# ANISMADriverBoard_v03.net
KiCad netlist of a schematic drawn in EAGLE
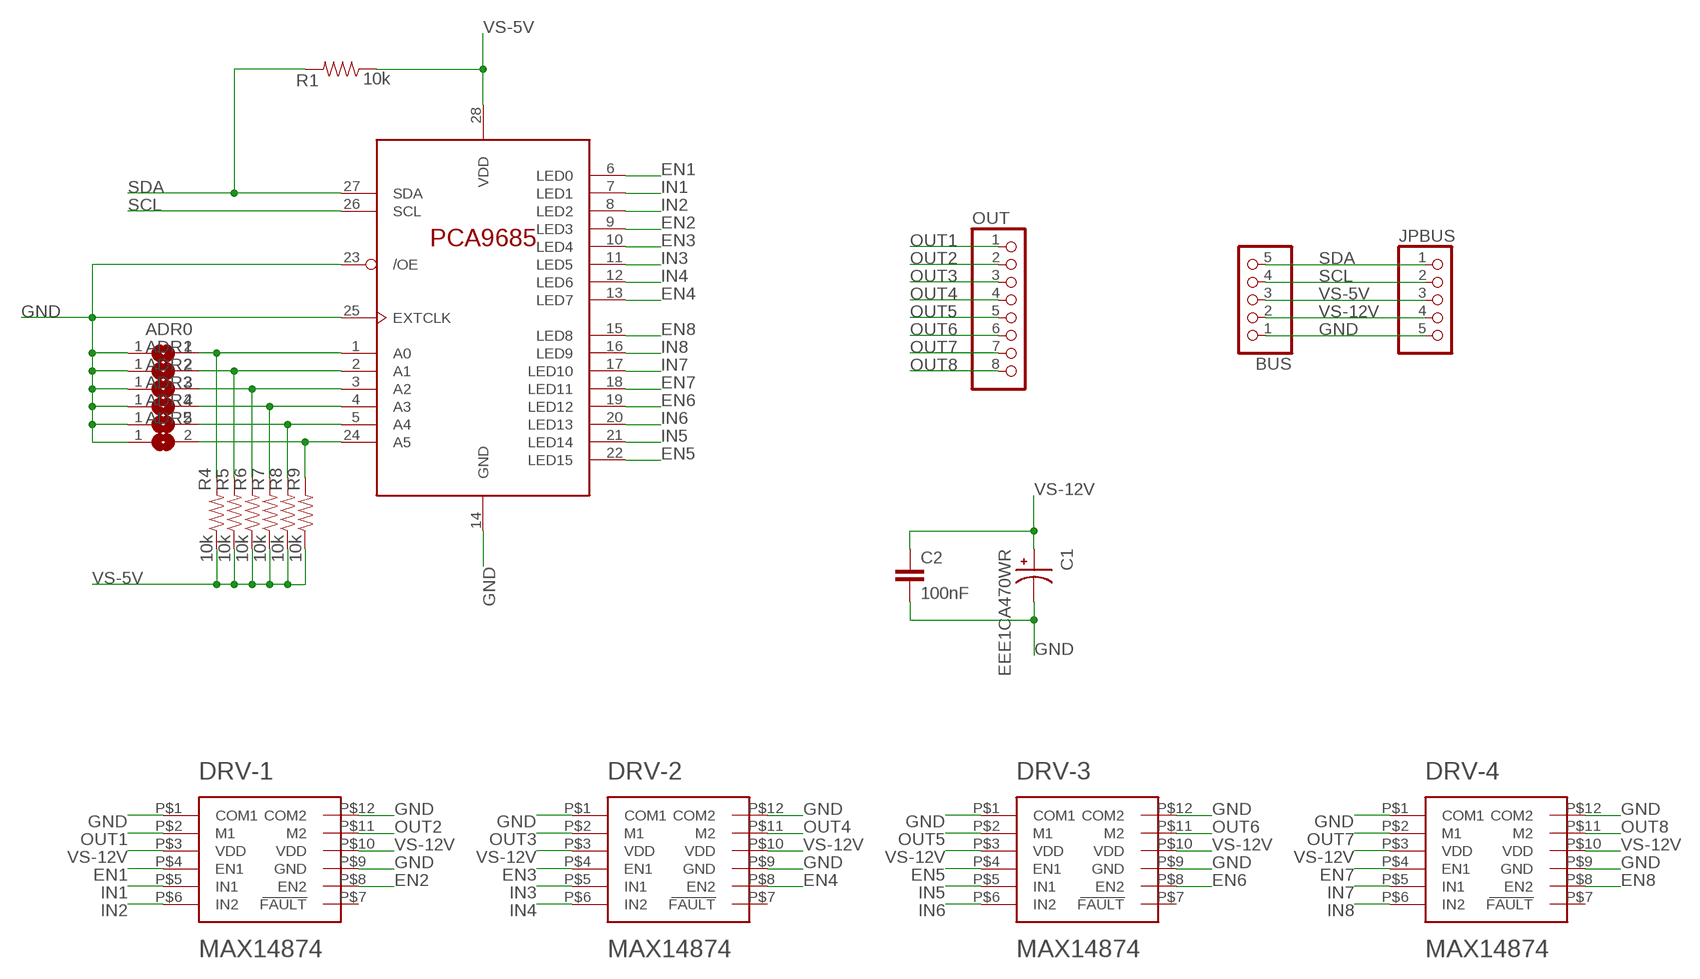
[diagram p0: schematic, sheet 1]

(export (version "E")
  (design (tool "Eeschema 10.0.6"))
  (components
    (comp (ref "ADR0")
      (value "SJ")
      (footprint "eagle-import:SJ")
      (libsource (lib "eagle-import") (part "SJ"))
    )
    (comp (ref "ADR1")
      (value "SJ")
      (footprint "eagle-import:SJ")
      (libsource (lib "eagle-import") (part "SJ"))
    )
    (comp (ref "ADR2")
      (value "SJ")
      (footprint "eagle-import:SJ")
      (libsource (lib "eagle-import") (part "SJ"))
    )
    (comp (ref "ADR3")
      (value "SJ")
      (footprint "eagle-import:SJ")
      (libsource (lib "eagle-import") (part "SJ"))
    )
    (comp (ref "ADR4")
      (value "SJ")
      (footprint "eagle-import:SJ")
      (libsource (lib "eagle-import") (part "SJ"))
    )
    (comp (ref "ADR5")
      (value "SJ")
      (footprint "eagle-import:SJ")
      (libsource (lib "eagle-import") (part "SJ"))
    )
    (comp (ref "BUS")
      (value "PINHD-1X5/90")
      (footprint "eagle-import:1X05_90")
      (libsource (lib "eagle-import") (part "PINHD-1X5/90"))
    )
    (comp (ref "C1")
      (value "EEE1CA470WR")
      (footprint "eagle-import:CAP_EEE1CA470WR")
      (fields (field (name "MF") "Panasonic Electronic") (field (name "MP") "EEE-1CA470WR"))
      (libsource (lib "eagle-import") (part "EEE1CA470WR"))
    )
    (comp (ref "C2")
      (value "100nF")
      (footprint "eagle-import:C0603")
      (libsource (lib "eagle-import") (part "C-EUC0603"))
    )
    (comp (ref "DRV-1")
      (value "MAX14874")
      (footprint "eagle-import:TD1233")
      (libsource (lib "eagle-import") (part "MAX14874"))
    )
    (comp (ref "DRV-2")
      (value "MAX14874")
      (footprint "eagle-import:TD1233")
      (libsource (lib "eagle-import") (part "MAX14874"))
    )
    (comp (ref "DRV-3")
      (value "MAX14874")
      (footprint "eagle-import:TD1233")
      (libsource (lib "eagle-import") (part "MAX14874"))
    )
    (comp (ref "DRV-4")
      (value "MAX14874")
      (footprint "eagle-import:TD1233")
      (libsource (lib "eagle-import") (part "MAX14874"))
    )
    (comp (ref "JPBUS")
      (value "PINHD-1X5/90")
      (footprint "eagle-import:1X05_90")
      (libsource (lib "eagle-import") (part "PINHD-1X5/90"))
    )
    (comp (ref "OUT")
      (value "PINHD-1X8/90")
      (footprint "eagle-import:1X08_90")
      (libsource (lib "eagle-import") (part "PINHD-1X8/90"))
    )
    (comp (ref "PCA9685")
      (value "PCA9685PW")
      (footprint "eagle-import:TSSOP28")
      (libsource (lib "eagle-import") (part "PCA9685PW"))
    )
    (comp (ref "R1")
      (value "10k")
      (footprint "eagle-import:0603")
      (fields (field (name "SPICEPREFIX") "R"))
      (libsource (lib "eagle-import") (part "10KOHM-0603-1/10W-1%"))
    )
    (comp (ref "R4")
      (value "10k")
      (footprint "eagle-import:0603")
      (fields (field (name "SPICEPREFIX") "R"))
      (libsource (lib "eagle-import") (part "10KOHM-0603-1/10W-1%"))
    )
    (comp (ref "R5")
      (value "10k")
      (footprint "eagle-import:0603")
      (fields (field (name "SPICEPREFIX") "R"))
      (libsource (lib "eagle-import") (part "10KOHM-0603-1/10W-1%"))
    )
    (comp (ref "R6")
      (value "10k")
      (footprint "eagle-import:0603")
      (fields (field (name "SPICEPREFIX") "R"))
      (libsource (lib "eagle-import") (part "10KOHM-0603-1/10W-1%"))
    )
    (comp (ref "R7")
      (value "10k")
      (footprint "eagle-import:0603")
      (fields (field (name "SPICEPREFIX") "R"))
      (libsource (lib "eagle-import") (part "10KOHM-0603-1/10W-1%"))
    )
    (comp (ref "R8")
      (value "10k")
      (footprint "eagle-import:0603")
      (fields (field (name "SPICEPREFIX") "R"))
      (libsource (lib "eagle-import") (part "10KOHM-0603-1/10W-1%"))
    )
    (comp (ref "R9")
      (value "10k")
      (footprint "eagle-import:0603")
      (fields (field (name "SPICEPREFIX") "R"))
      (libsource (lib "eagle-import") (part "10KOHM-0603-1/10W-1%"))
    )
  )
  (nets
    (net (code "1") (name "/EN1") (class "Default")
      (node (ref "DRV-1") (pin "P$4") (pinfunction "EN1_P$4") (pintype "bidirectional"))
      (node (ref "PCA9685") (pin "6") (pinfunction "LED0_6") (pintype "bidirectional"))
    )
    (net (code "2") (name "/EN2") (class "Default")
      (node (ref "DRV-1") (pin "P$8") (pinfunction "EN2_P$8") (pintype "bidirectional"))
      (node (ref "PCA9685") (pin "9") (pinfunction "LED3_9") (pintype "bidirectional"))
    )
    (net (code "3") (name "/EN3") (class "Default")
      (node (ref "DRV-2") (pin "P$4") (pinfunction "EN1_P$4") (pintype "bidirectional"))
      (node (ref "PCA9685") (pin "10") (pinfunction "LED4_10") (pintype "bidirectional"))
    )
    (net (code "4") (name "/EN4") (class "Default")
      (node (ref "DRV-2") (pin "P$8") (pinfunction "EN2_P$8") (pintype "bidirectional"))
      (node (ref "PCA9685") (pin "13") (pinfunction "LED7_13") (pintype "bidirectional"))
    )
    (net (code "5") (name "/EN5") (class "Default")
      (node (ref "DRV-3") (pin "P$4") (pinfunction "EN1_P$4") (pintype "bidirectional"))
      (node (ref "PCA9685") (pin "22") (pinfunction "LED15_22") (pintype "bidirectional"))
    )
    (net (code "6") (name "/EN6") (class "Default")
      (node (ref "DRV-3") (pin "P$8") (pinfunction "EN2_P$8") (pintype "bidirectional"))
      (node (ref "PCA9685") (pin "19") (pinfunction "LED12_19") (pintype "bidirectional"))
    )
    (net (code "7") (name "/EN7") (class "Default")
      (node (ref "DRV-4") (pin "P$4") (pinfunction "EN1_P$4") (pintype "bidirectional"))
      (node (ref "PCA9685") (pin "18") (pinfunction "LED11_18") (pintype "bidirectional"))
    )
    (net (code "8") (name "/EN8") (class "Default")
      (node (ref "DRV-4") (pin "P$8") (pinfunction "EN2_P$8") (pintype "bidirectional"))
      (node (ref "PCA9685") (pin "15") (pinfunction "LED8_15") (pintype "bidirectional"))
    )
    (net (code "9") (name "/GND") (class "Default")
      (node (ref "ADR0") (pin "1") (pinfunction "1_1") (pintype "passive"))
      (node (ref "ADR1") (pin "1") (pinfunction "1_1") (pintype "passive"))
      (node (ref "ADR2") (pin "1") (pinfunction "1_1") (pintype "passive"))
      (node (ref "ADR3") (pin "1") (pinfunction "1_1") (pintype "passive"))
      (node (ref "ADR4") (pin "1") (pinfunction "1_1") (pintype "passive"))
      (node (ref "ADR5") (pin "1") (pinfunction "1_1") (pintype "passive"))
      (node (ref "BUS") (pin "1") (pinfunction "1_1") (pintype "passive"))
      (node (ref "C1") (pin "2") (pinfunction "2_2") (pintype "passive"))
      (node (ref "C2") (pin "2") (pinfunction "2_2") (pintype "passive"))
      (node (ref "DRV-1") (pin "P$1") (pinfunction "COM1_P$1") (pintype "bidirectional"))
      (node (ref "DRV-1") (pin "P$12") (pinfunction "COM2_P$12") (pintype "bidirectional"))
      (node (ref "DRV-1") (pin "P$9") (pinfunction "GND_P$9") (pintype "bidirectional"))
      (node (ref "DRV-2") (pin "P$1") (pinfunction "COM1_P$1") (pintype "bidirectional"))
      (node (ref "DRV-2") (pin "P$12") (pinfunction "COM2_P$12") (pintype "bidirectional"))
      (node (ref "DRV-2") (pin "P$9") (pinfunction "GND_P$9") (pintype "bidirectional"))
      (node (ref "DRV-3") (pin "P$1") (pinfunction "COM1_P$1") (pintype "bidirectional"))
      (node (ref "DRV-3") (pin "P$12") (pinfunction "COM2_P$12") (pintype "bidirectional"))
      (node (ref "DRV-3") (pin "P$9") (pinfunction "GND_P$9") (pintype "bidirectional"))
      (node (ref "DRV-4") (pin "P$1") (pinfunction "COM1_P$1") (pintype "bidirectional"))
      (node (ref "DRV-4") (pin "P$12") (pinfunction "COM2_P$12") (pintype "bidirectional"))
      (node (ref "DRV-4") (pin "P$9") (pinfunction "GND_P$9") (pintype "bidirectional"))
      (node (ref "JPBUS") (pin "5") (pinfunction "5_5") (pintype "passive"))
      (node (ref "PCA9685") (pin "14") (pinfunction "GND_14") (pintype "power_in"))
      (node (ref "PCA9685") (pin "23") (pinfunction "/OE_23") (pintype "bidirectional"))
      (node (ref "PCA9685") (pin "25") (pinfunction "EXTCLK_25") (pintype "input"))
    )
    (net (code "10") (name "/IN1") (class "Default")
      (node (ref "DRV-1") (pin "P$5") (pinfunction "IN1_P$5") (pintype "bidirectional"))
      (node (ref "PCA9685") (pin "7") (pinfunction "LED1_7") (pintype "bidirectional"))
    )
    (net (code "11") (name "/IN2") (class "Default")
      (node (ref "DRV-1") (pin "P$6") (pinfunction "IN2_P$6") (pintype "bidirectional"))
      (node (ref "PCA9685") (pin "8") (pinfunction "LED2_8") (pintype "bidirectional"))
    )
    (net (code "12") (name "/IN3") (class "Default")
      (node (ref "DRV-2") (pin "P$5") (pinfunction "IN1_P$5") (pintype "bidirectional"))
      (node (ref "PCA9685") (pin "11") (pinfunction "LED5_11") (pintype "bidirectional"))
    )
    (net (code "13") (name "/IN4") (class "Default")
      (node (ref "DRV-2") (pin "P$6") (pinfunction "IN2_P$6") (pintype "bidirectional"))
      (node (ref "PCA9685") (pin "12") (pinfunction "LED6_12") (pintype "bidirectional"))
    )
    (net (code "14") (name "/IN5") (class "Default")
      (node (ref "DRV-3") (pin "P$5") (pinfunction "IN1_P$5") (pintype "bidirectional"))
      (node (ref "PCA9685") (pin "21") (pinfunction "LED14_21") (pintype "bidirectional"))
    )
    (net (code "15") (name "/IN6") (class "Default")
      (node (ref "DRV-3") (pin "P$6") (pinfunction "IN2_P$6") (pintype "bidirectional"))
      (node (ref "PCA9685") (pin "20") (pinfunction "LED13_20") (pintype "bidirectional"))
    )
    (net (code "16") (name "/IN7") (class "Default")
      (node (ref "DRV-4") (pin "P$5") (pinfunction "IN1_P$5") (pintype "bidirectional"))
      (node (ref "PCA9685") (pin "17") (pinfunction "LED10_17") (pintype "bidirectional"))
    )
    (net (code "17") (name "/IN8") (class "Default")
      (node (ref "DRV-4") (pin "P$6") (pinfunction "IN2_P$6") (pintype "bidirectional"))
      (node (ref "PCA9685") (pin "16") (pinfunction "LED9_16") (pintype "bidirectional"))
    )
    (net (code "18") (name "/OUT1") (class "Default")
      (node (ref "DRV-1") (pin "P$2") (pinfunction "M1_P$2") (pintype "bidirectional"))
      (node (ref "OUT") (pin "1") (pinfunction "1_1") (pintype "passive"))
    )
    (net (code "19") (name "/OUT2") (class "Default")
      (node (ref "DRV-1") (pin "P$11") (pinfunction "M2_P$11") (pintype "bidirectional"))
      (node (ref "OUT") (pin "2") (pinfunction "2_2") (pintype "passive"))
    )
    (net (code "20") (name "/OUT3") (class "Default")
      (node (ref "DRV-2") (pin "P$2") (pinfunction "M1_P$2") (pintype "bidirectional"))
      (node (ref "OUT") (pin "3") (pinfunction "3_3") (pintype "passive"))
    )
    (net (code "21") (name "/OUT4") (class "Default")
      (node (ref "DRV-2") (pin "P$11") (pinfunction "M2_P$11") (pintype "bidirectional"))
      (node (ref "OUT") (pin "4") (pinfunction "4_4") (pintype "passive"))
    )
    (net (code "22") (name "/OUT5") (class "Default")
      (node (ref "DRV-3") (pin "P$2") (pinfunction "M1_P$2") (pintype "bidirectional"))
      (node (ref "OUT") (pin "5") (pinfunction "5_5") (pintype "passive"))
    )
    (net (code "23") (name "/OUT6") (class "Default")
      (node (ref "DRV-3") (pin "P$11") (pinfunction "M2_P$11") (pintype "bidirectional"))
      (node (ref "OUT") (pin "6") (pinfunction "6_6") (pintype "passive"))
    )
    (net (code "24") (name "/OUT7") (class "Default")
      (node (ref "DRV-4") (pin "P$2") (pinfunction "M1_P$2") (pintype "bidirectional"))
      (node (ref "OUT") (pin "7") (pinfunction "7_7") (pintype "passive"))
    )
    (net (code "25") (name "/OUT8") (class "Default")
      (node (ref "DRV-4") (pin "P$11") (pinfunction "M2_P$11") (pintype "bidirectional"))
      (node (ref "OUT") (pin "8") (pinfunction "8_8") (pintype "passive"))
    )
    (net (code "26") (name "/SCL") (class "Default")
      (node (ref "BUS") (pin "4") (pinfunction "4_4") (pintype "passive"))
      (node (ref "JPBUS") (pin "2") (pinfunction "2_2") (pintype "passive"))
      (node (ref "PCA9685") (pin "26") (pinfunction "SCL_26") (pintype "bidirectional"))
    )
    (net (code "27") (name "/SDA") (class "Default")
      (node (ref "BUS") (pin "5") (pinfunction "5_5") (pintype "passive"))
      (node (ref "JPBUS") (pin "1") (pinfunction "1_1") (pintype "passive"))
      (node (ref "PCA9685") (pin "27") (pinfunction "SDA_27") (pintype "bidirectional"))
      (node (ref "R1") (pin "2") (pinfunction "2_2") (pintype "passive"))
    )
    (net (code "28") (name "/VS-5V") (class "Default")
      (node (ref "BUS") (pin "3") (pinfunction "3_3") (pintype "passive"))
      (node (ref "JPBUS") (pin "3") (pinfunction "3_3") (pintype "passive"))
      (node (ref "PCA9685") (pin "28") (pinfunction "VDD_28") (pintype "power_in"))
      (node (ref "R1") (pin "1") (pinfunction "1_1") (pintype "passive"))
      (node (ref "R4") (pin "1") (pinfunction "1_1") (pintype "passive"))
      (node (ref "R5") (pin "1") (pinfunction "1_1") (pintype "passive"))
      (node (ref "R6") (pin "1") (pinfunction "1_1") (pintype "passive"))
      (node (ref "R7") (pin "1") (pinfunction "1_1") (pintype "passive"))
      (node (ref "R8") (pin "1") (pinfunction "1_1") (pintype "passive"))
      (node (ref "R9") (pin "1") (pinfunction "1_1") (pintype "passive"))
    )
    (net (code "29") (name "/VS-12V") (class "Default")
      (node (ref "BUS") (pin "2") (pinfunction "2_2") (pintype "passive"))
      (node (ref "C1") (pin "1") (pinfunction "1_1") (pintype "passive"))
      (node (ref "C2") (pin "1") (pinfunction "1_1") (pintype "passive"))
      (node (ref "DRV-1") (pin "P$10") (pinfunction "VDD_P$10") (pintype "bidirectional"))
      (node (ref "DRV-1") (pin "P$3") (pinfunction "VDD_P$3") (pintype "bidirectional"))
      (node (ref "DRV-2") (pin "P$10") (pinfunction "VDD_P$10") (pintype "bidirectional"))
      (node (ref "DRV-2") (pin "P$3") (pinfunction "VDD_P$3") (pintype "bidirectional"))
      (node (ref "DRV-3") (pin "P$10") (pinfunction "VDD_P$10") (pintype "bidirectional"))
      (node (ref "DRV-3") (pin "P$3") (pinfunction "VDD_P$3") (pintype "bidirectional"))
      (node (ref "DRV-4") (pin "P$10") (pinfunction "VDD_P$10") (pintype "bidirectional"))
      (node (ref "DRV-4") (pin "P$3") (pinfunction "VDD_P$3") (pintype "bidirectional"))
      (node (ref "JPBUS") (pin "4") (pinfunction "4_4") (pintype "passive"))
    )
    (net (code "30") (name "Net-(PCA9685-A0)") (class "Default")
      (node (ref "ADR0") (pin "2") (pinfunction "2_2") (pintype "passive"))
      (node (ref "PCA9685") (pin "1") (pinfunction "A0_1") (pintype "bidirectional"))
      (node (ref "R4") (pin "2") (pinfunction "2_2") (pintype "passive"))
    )
    (net (code "31") (name "Net-(PCA9685-A1)") (class "Default")
      (node (ref "ADR1") (pin "2") (pinfunction "2_2") (pintype "passive"))
      (node (ref "PCA9685") (pin "2") (pinfunction "A1_2") (pintype "bidirectional"))
      (node (ref "R5") (pin "2") (pinfunction "2_2") (pintype "passive"))
    )
    (net (code "32") (name "Net-(PCA9685-A2)") (class "Default")
      (node (ref "ADR2") (pin "2") (pinfunction "2_2") (pintype "passive"))
      (node (ref "PCA9685") (pin "3") (pinfunction "A2_3") (pintype "bidirectional"))
      (node (ref "R6") (pin "2") (pinfunction "2_2") (pintype "passive"))
    )
    (net (code "33") (name "Net-(PCA9685-A3)") (class "Default")
      (node (ref "ADR3") (pin "2") (pinfunction "2_2") (pintype "passive"))
      (node (ref "PCA9685") (pin "4") (pinfunction "A3_4") (pintype "bidirectional"))
      (node (ref "R7") (pin "2") (pinfunction "2_2") (pintype "passive"))
    )
    (net (code "34") (name "Net-(PCA9685-A4)") (class "Default")
      (node (ref "ADR4") (pin "2") (pinfunction "2_2") (pintype "passive"))
      (node (ref "PCA9685") (pin "5") (pinfunction "A4_5") (pintype "bidirectional"))
      (node (ref "R8") (pin "2") (pinfunction "2_2") (pintype "passive"))
    )
    (net (code "35") (name "Net-(PCA9685-A5)") (class "Default")
      (node (ref "ADR5") (pin "2") (pinfunction "2_2") (pintype "passive"))
      (node (ref "PCA9685") (pin "24") (pinfunction "A5_24") (pintype "bidirectional"))
      (node (ref "R9") (pin "2") (pinfunction "2_2") (pintype "passive"))
    )
    (net (code "36") (name "unconnected-(DRV-1-FAULT-PadP$7)") (class "Default")
      (node (ref "DRV-1") (pin "P$7") (pinfunction "FAULT_P$7") (pintype "bidirectional"))
    )
    (net (code "37") (name "unconnected-(DRV-2-FAULT-PadP$7)") (class "Default")
      (node (ref "DRV-2") (pin "P$7") (pinfunction "FAULT_P$7") (pintype "bidirectional"))
    )
    (net (code "38") (name "unconnected-(DRV-3-FAULT-PadP$7)") (class "Default")
      (node (ref "DRV-3") (pin "P$7") (pinfunction "FAULT_P$7") (pintype "bidirectional"))
    )
    (net (code "39") (name "unconnected-(DRV-4-FAULT-PadP$7)") (class "Default")
      (node (ref "DRV-4") (pin "P$7") (pinfunction "FAULT_P$7") (pintype "bidirectional"))
    )
  )
)
